# Display_Module.net
KiCad netlist of a schematic drawn in Altium Designer
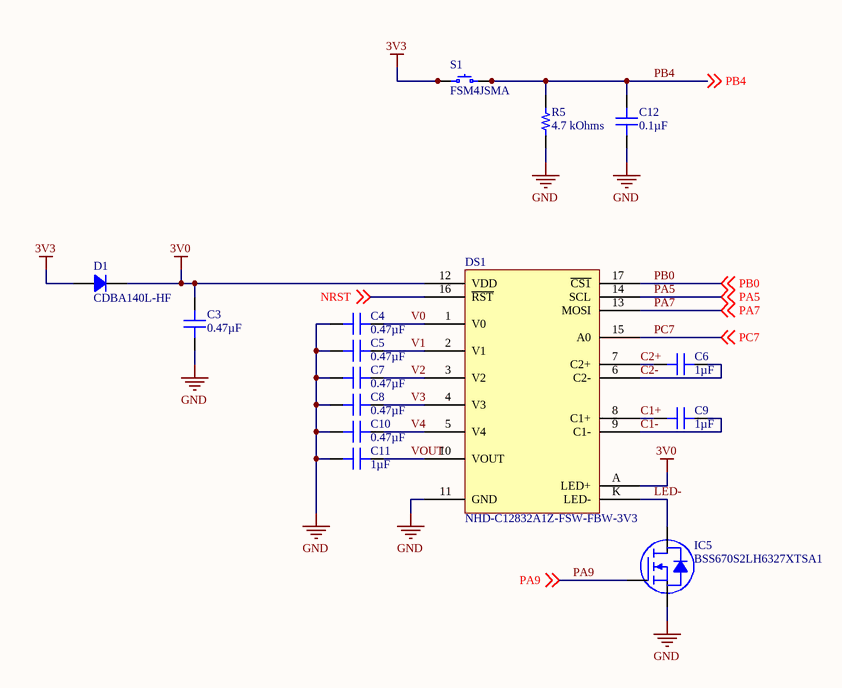
[diagram p0: Display Module.SchDoc]

(export (version "E")
  (design (tool "Eeschema 10.0.6"))
  (components
    (comp (ref "C3")
      (value "0.47µF")
      (footprint "CAP 0603_1608")
      (description "CAP CER 0.47UF 10V X7R 0603")
      (fields
        (field (name "PART NUMBER") "0603B474K100CT")
        (field (name "MANUFACTURER") "Walsin Technology Corporation")
      )
      (libsource (lib "altiumlibrary.com") (part "Capacitor"))
    )
    (comp (ref "C4")
      (value "0.47µF")
      (footprint "CAP 0603_1608")
      (description "CAP CER 0.47UF 10V X7R 0603")
      (fields
        (field (name "PART NUMBER") "0603B474K100CT")
        (field (name "MANUFACTURER") "Walsin Technology Corporation")
      )
      (libsource (lib "altiumlibrary.com") (part "Capacitor"))
    )
    (comp (ref "C5")
      (value "0.47µF")
      (footprint "CAP 0603_1608")
      (description "CAP CER 0.47UF 10V X7R 0603")
      (fields
        (field (name "PART NUMBER") "0603B474K100CT")
        (field (name "MANUFACTURER") "Walsin Technology Corporation")
      )
      (libsource (lib "altiumlibrary.com") (part "Capacitor"))
    )
    (comp (ref "C6")
      (value "1µF")
      (footprint "CAP 0603_1608")
      (description "CAP CER 1UF 10V X7R 0603")
      (fields (field (name "PART NUMBER") "LMK107B7105KA-T") (field (name "MANUFACTURER") "Taiyo Yuden"))
      (libsource (lib "altiumlibrary.com") (part "Capacitor"))
    )
    (comp (ref "C7")
      (value "0.47µF")
      (footprint "CAP 0603_1608")
      (description "CAP CER 0.47UF 10V X7R 0603")
      (fields
        (field (name "PART NUMBER") "0603B474K100CT")
        (field (name "MANUFACTURER") "Walsin Technology Corporation")
      )
      (libsource (lib "altiumlibrary.com") (part "Capacitor"))
    )
    (comp (ref "C8")
      (value "0.47µF")
      (footprint "CAP 0603_1608")
      (description "CAP CER 0.47UF 10V X7R 0603")
      (fields
        (field (name "PART NUMBER") "0603B474K100CT")
        (field (name "MANUFACTURER") "Walsin Technology Corporation")
      )
      (libsource (lib "altiumlibrary.com") (part "Capacitor"))
    )
    (comp (ref "C9")
      (value "1µF")
      (footprint "CAP 0603_1608")
      (description "CAP CER 1UF 10V X7R 0603")
      (fields (field (name "PART NUMBER") "LMK107B7105KA-T") (field (name "MANUFACTURER") "Taiyo Yuden"))
      (libsource (lib "altiumlibrary.com") (part "Capacitor"))
    )
    (comp (ref "C10")
      (value "0.47µF")
      (footprint "CAP 0603_1608")
      (description "CAP CER 0.47UF 10V X7R 0603")
      (fields
        (field (name "PART NUMBER") "0603B474K100CT")
        (field (name "MANUFACTURER") "Walsin Technology Corporation")
      )
      (libsource (lib "altiumlibrary.com") (part "Capacitor"))
    )
    (comp (ref "C11")
      (value "1µF")
      (footprint "CAP 0603_1608")
      (description "CAP CER 1UF 10V X7R 0603")
      (fields (field (name "PART NUMBER") "LMK107B7105KA-T") (field (name "MANUFACTURER") "Taiyo Yuden"))
      (libsource (lib "altiumlibrary.com") (part "Capacitor"))
    )
    (comp (ref "C12")
      (value "0.1µF")
      (footprint "CAP 0603_1608")
      (description "CAP CER 0.1UF 50V X7R 0603")
      (fields (field (name "PART NUMBER") "06035C104JAT4A") (field (name "MANUFACTURER") "AVX Corporation"))
      (libsource (lib "altiumlibrary.com") (part "Capacitor"))
    )
    (comp (ref "D1")
      (value "CDBA140L-HF")
      (footprint "DO214AC SMA")
      (description "DIODE SCHOTTKY 40V 1A DO214AC")
      (fields (field (name "MANUFACTURER") "Comchip Technology"))
      (libsource (lib "altiumlibrary.com") (part "Diode"))
    )
    (comp (ref "DS1")
      (value "NHD-C12832A1Z-FSW-FBW-3V3")
      (footprint "NHD-C12832A1Z WHITE")
      (description "LCD COG GRAPHIC 128X32")
      (fields (field (name "MANUFACTURER") "Newhaven Display Intl"))
      (libsource (lib "altiumlibrary.com") (part "Newhaven NHD-C12832A1Z"))
    )
    (comp (ref "IC5")
      (value "BSS670S2LH6327XTSA1")
      (footprint "INFINEON SOT-23-3")
      (description "MOSFET N-CH 55V 540MA SOT23")
      (fields (field (name "MANUFACTURER") "Infineon Technologies"))
      (libsource (lib "altiumlibrary.com") (part "INFINEON MOSFET N-CH SOT-23-3 GSD"))
    )
    (comp (ref "R5")
      (value "4.7 kOhms")
      (footprint "RES 0603_1608")
      (description "RES SMD 4.7K OHM 1% 1/10W 0603")
      (fields
        (field (name "PART NUMBER") "ERJ-3EKF4701V")
        (field (name "MANUFACTURER") "Panasonic Electronic Components")
      )
      (libsource (lib "altiumlibrary.com") (part "Resistor"))
    )
    (comp (ref "S1")
      (value "FSM4JSMA")
      (footprint "TE FSM4JSMA")
      (description "SWITCH TACTILE SPST-NO 0.05A 24V")
      (fields (field (name "MANUFACTURER") "TE Connectivity ALCOSWITCH Switches"))
      (libsource (lib "altiumlibrary.com") (part "SPST-NO 4 PIN"))
    )
  )
  (nets
    (net (code "1") (name "/C1+") (class "Default")
      (node (ref "C9") (pin "1") (pinfunction "1_1") (pintype "passive"))
      (node (ref "DS1") (pin "8") (pinfunction "C1+_8") (pintype "passive"))
    )
    (net (code "2") (name "/C1-") (class "Default")
      (node (ref "C9") (pin "2") (pinfunction "2_2") (pintype "passive"))
      (node (ref "DS1") (pin "9") (pinfunction "C1-_9") (pintype "passive"))
    )
    (net (code "3") (name "/C2+") (class "Default")
      (node (ref "C6") (pin "1") (pinfunction "1_1") (pintype "passive"))
      (node (ref "DS1") (pin "7") (pinfunction "C2+_7") (pintype "passive"))
    )
    (net (code "4") (name "/C2-") (class "Default")
      (node (ref "C6") (pin "2") (pinfunction "2_2") (pintype "passive"))
      (node (ref "DS1") (pin "6") (pinfunction "C2-_6") (pintype "passive"))
    )
    (net (code "5") (name "/LED-") (class "Default")
      (node (ref "DS1") (pin "K") (pinfunction "LED-_K") (pintype "passive"))
      (node (ref "IC5") (pin "3") (pinfunction "D_3") (pintype "passive"))
    )
    (net (code "6") (name "/V0") (class "Default")
      (node (ref "C4") (pin "1") (pinfunction "1_1") (pintype "passive"))
      (node (ref "DS1") (pin "1") (pinfunction "V0_1") (pintype "passive"))
    )
    (net (code "7") (name "/V1") (class "Default")
      (node (ref "C5") (pin "1") (pinfunction "1_1") (pintype "passive"))
      (node (ref "DS1") (pin "2") (pinfunction "V1_2") (pintype "passive"))
    )
    (net (code "8") (name "/V2") (class "Default")
      (node (ref "C7") (pin "1") (pinfunction "1_1") (pintype "passive"))
      (node (ref "DS1") (pin "3") (pinfunction "V2_3") (pintype "passive"))
    )
    (net (code "9") (name "/V3") (class "Default")
      (node (ref "C8") (pin "1") (pinfunction "1_1") (pintype "passive"))
      (node (ref "DS1") (pin "4") (pinfunction "V3_4") (pintype "passive"))
    )
    (net (code "10") (name "/V4") (class "Default")
      (node (ref "C10") (pin "1") (pinfunction "1_1") (pintype "passive"))
      (node (ref "DS1") (pin "5") (pinfunction "V4_5") (pintype "passive"))
    )
    (net (code "11") (name "/VOUT") (class "Default")
      (node (ref "C11") (pin "2") (pinfunction "2_2") (pintype "passive"))
      (node (ref "DS1") (pin "10") (pinfunction "VOUT_10") (pintype "passive"))
    )
    (net (code "12") (name "3V0") (class "Default")
      (node (ref "C3") (pin "1") (pinfunction "1_1") (pintype "passive"))
      (node (ref "D1") (pin "2") (pinfunction "2_2") (pintype "passive"))
      (node (ref "DS1") (pin "12") (pinfunction "VDD_12") (pintype "passive"))
      (node (ref "DS1") (pin "A") (pinfunction "LED+_A") (pintype "passive"))
    )
    (net (code "13") (name "3V3") (class "Default")
      (node (ref "D1") (pin "1") (pinfunction "1_1") (pintype "passive"))
      (node (ref "S1") (pin "1") (pinfunction "1_1") (pintype "passive"))
      (node (ref "S1") (pin "2") (pinfunction "2_2") (pintype "passive"))
    )
    (net (code "14") (name "GND") (class "Default")
      (node (ref "C10") (pin "2") (pinfunction "2_2") (pintype "passive"))
      (node (ref "C11") (pin "1") (pinfunction "1_1") (pintype "passive"))
      (node (ref "C12") (pin "1") (pinfunction "1_1") (pintype "passive"))
      (node (ref "C3") (pin "2") (pinfunction "2_2") (pintype "passive"))
      (node (ref "C4") (pin "2") (pinfunction "2_2") (pintype "passive"))
      (node (ref "C5") (pin "2") (pinfunction "2_2") (pintype "passive"))
      (node (ref "C7") (pin "2") (pinfunction "2_2") (pintype "passive"))
      (node (ref "C8") (pin "2") (pinfunction "2_2") (pintype "passive"))
      (node (ref "DS1") (pin "11") (pinfunction "GND_11") (pintype "passive"))
      (node (ref "IC5") (pin "2") (pinfunction "S_2") (pintype "passive"))
      (node (ref "R5") (pin "1") (pinfunction "1_1") (pintype "passive"))
    )
    (net (code "15") (name "NRST") (class "Default")
      (node (ref "DS1") (pin "16") (pinfunction "~{RST}_16") (pintype "passive"))
    )
    (net (code "16") (name "PA5") (class "Default")
      (node (ref "DS1") (pin "14") (pinfunction "SCL_14") (pintype "passive"))
    )
    (net (code "17") (name "PA7") (class "Default")
      (node (ref "DS1") (pin "13") (pinfunction "MOSI_13") (pintype "passive"))
    )
    (net (code "18") (name "PA9") (class "Default")
      (node (ref "IC5") (pin "1") (pinfunction "G_1") (pintype "passive"))
    )
    (net (code "19") (name "PB0") (class "Default")
      (node (ref "DS1") (pin "17") (pinfunction "~{CS1}_17") (pintype "passive"))
    )
    (net (code "20") (name "PB4") (class "Default")
      (node (ref "C12") (pin "2") (pinfunction "2_2") (pintype "passive"))
      (node (ref "R5") (pin "2") (pinfunction "2_2") (pintype "passive"))
      (node (ref "S1") (pin "3") (pinfunction "3_3") (pintype "passive"))
      (node (ref "S1") (pin "4") (pinfunction "4_4") (pintype "passive"))
    )
    (net (code "21") (name "PC7") (class "Default")
      (node (ref "DS1") (pin "15") (pinfunction "A0_15") (pintype "passive"))
    )
  )
)
